# midi-switcher-dpdt.net
KiCad netlist of a schematic drawn in EAGLE
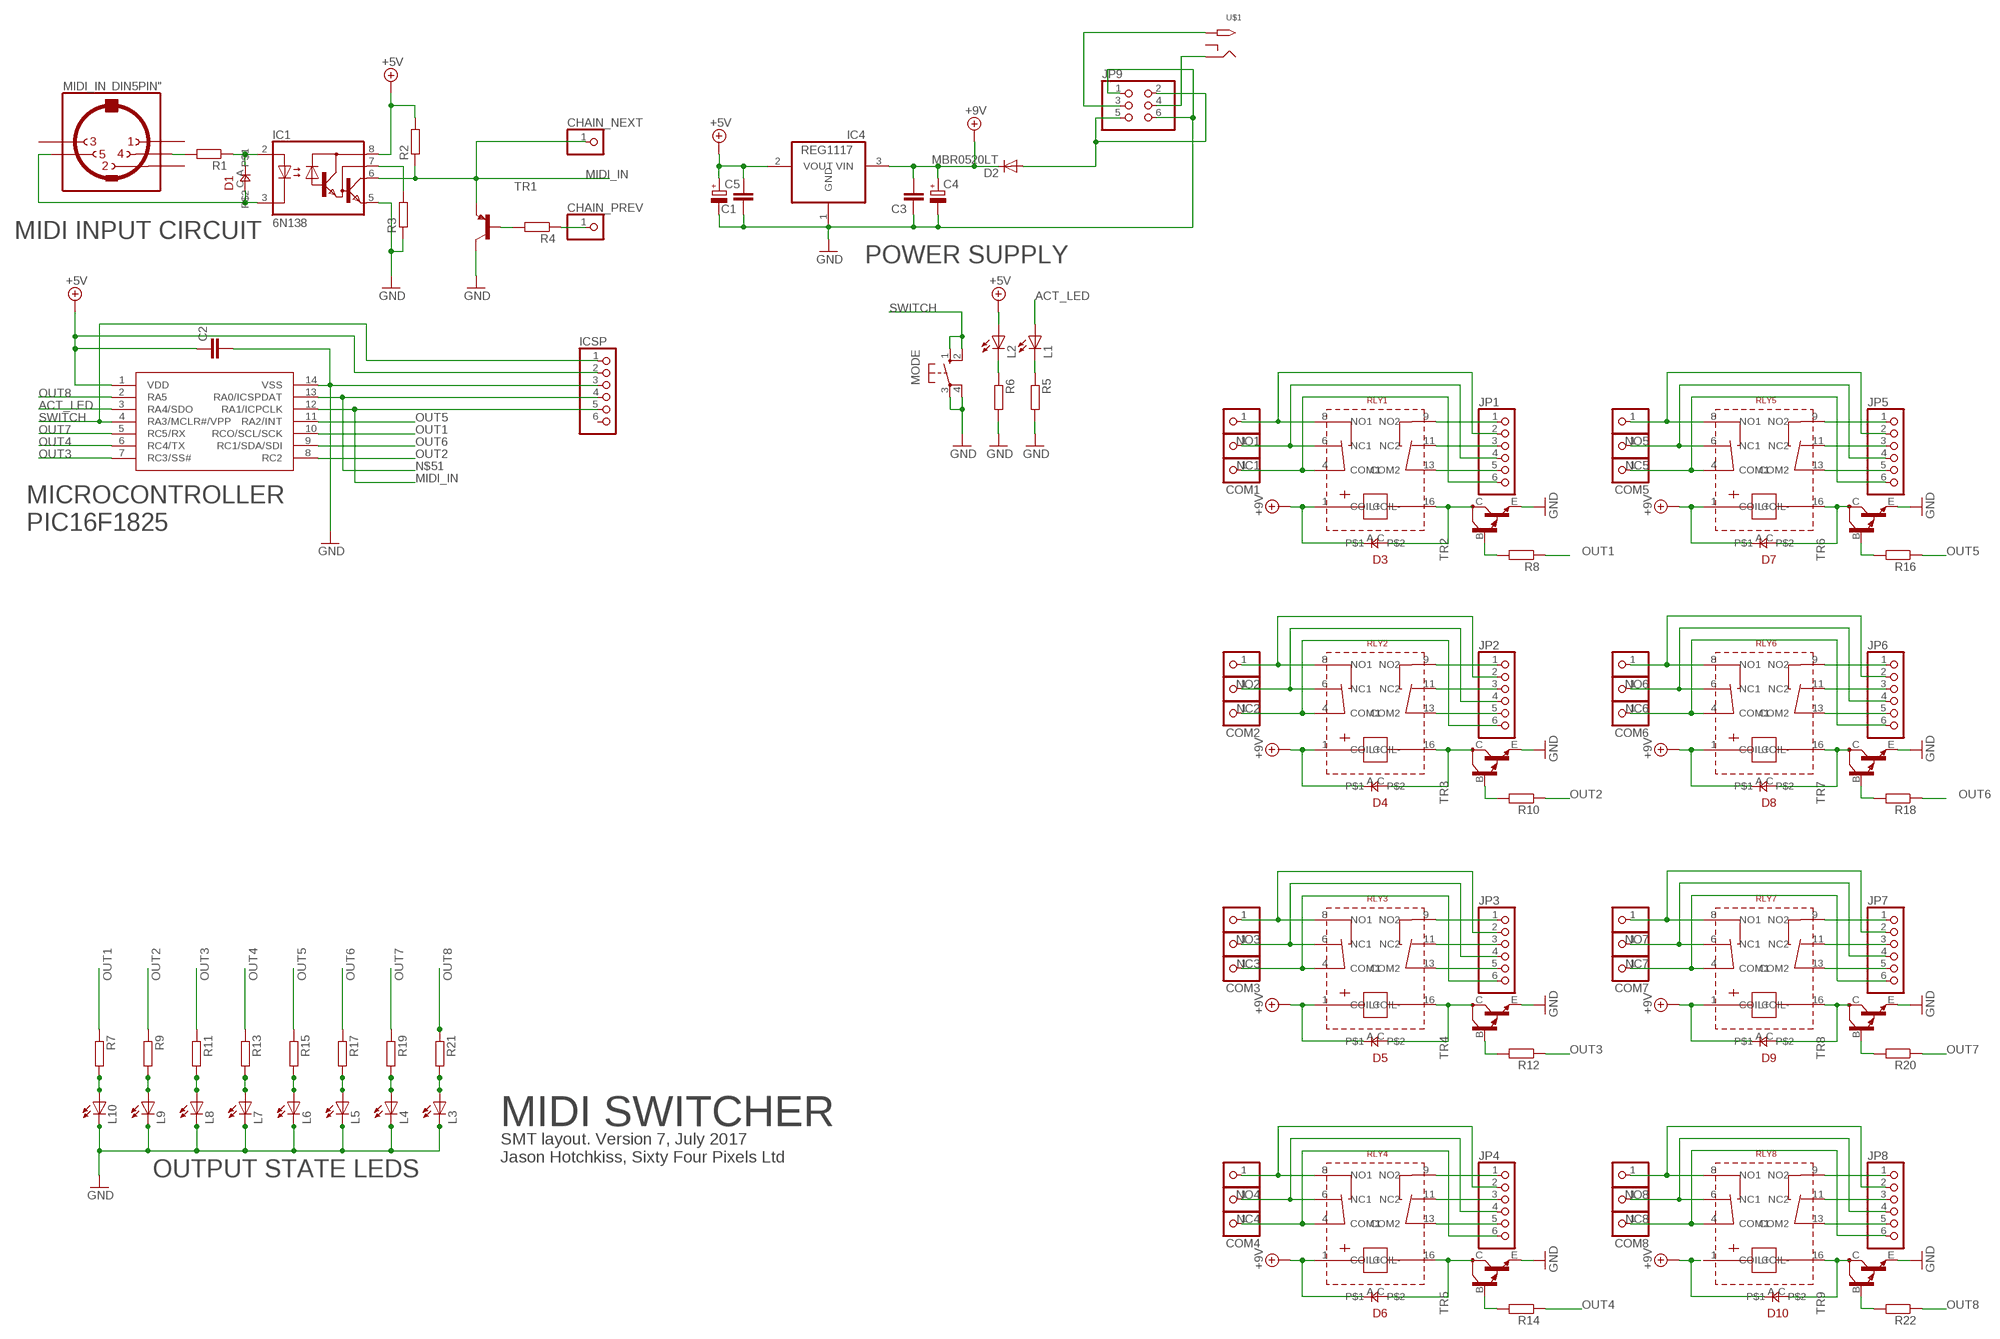
[diagram p0: schematic, sheet 1]

(export (version "E")
  (design (tool "Eeschema 10.0.6"))
  (components
    (comp (ref "C1")
      (value "C-EUC0805")
      (footprint "eagle-import:C0805")
      (libsource (lib "eagle-import") (part "C-EUC0805"))
    )
    (comp (ref "C2")
      (value "C-EUC0805")
      (footprint "eagle-import:C0805")
      (libsource (lib "eagle-import") (part "C-EUC0805"))
    )
    (comp (ref "C3")
      (value "C-EUC0805")
      (footprint "eagle-import:C0805")
      (libsource (lib "eagle-import") (part "C-EUC0805"))
    )
    (comp (ref "C4")
      (value "CPOL-EUE2,5-6E")
      (footprint "eagle-import:E2,5-6E")
      (libsource (lib "eagle-import") (part "CPOL-EUE2,5-6E"))
    )
    (comp (ref "C5")
      (value "CPOL-EUE2,5-6E")
      (footprint "eagle-import:E2,5-6E")
      (libsource (lib "eagle-import") (part "CPOL-EUE2,5-6E"))
    )
    (comp (ref "CHAIN_NEXT")
      (value "PINHD-1X1")
      (footprint "eagle-import:1X01")
      (libsource (lib "eagle-import") (part "PINHD-1X1"))
    )
    (comp (ref "CHAIN_PREV")
      (value "PINHD-1X1")
      (footprint "eagle-import:1X01")
      (libsource (lib "eagle-import") (part "PINHD-1X1"))
    )
    (comp (ref "COM1")
      (value "PINHD-1X1")
      (footprint "eagle-import:1X01")
      (libsource (lib "eagle-import") (part "PINHD-1X1"))
    )
    (comp (ref "COM2")
      (value "PINHD-1X1")
      (footprint "eagle-import:1X01")
      (libsource (lib "eagle-import") (part "PINHD-1X1"))
    )
    (comp (ref "COM3")
      (value "PINHD-1X1")
      (footprint "eagle-import:1X01")
      (libsource (lib "eagle-import") (part "PINHD-1X1"))
    )
    (comp (ref "COM4")
      (value "PINHD-1X1")
      (footprint "eagle-import:1X01")
      (libsource (lib "eagle-import") (part "PINHD-1X1"))
    )
    (comp (ref "COM5")
      (value "PINHD-1X1")
      (footprint "eagle-import:1X01")
      (libsource (lib "eagle-import") (part "PINHD-1X1"))
    )
    (comp (ref "COM6")
      (value "PINHD-1X1")
      (footprint "eagle-import:1X01")
      (libsource (lib "eagle-import") (part "PINHD-1X1"))
    )
    (comp (ref "COM7")
      (value "PINHD-1X1")
      (footprint "eagle-import:1X01")
      (libsource (lib "eagle-import") (part "PINHD-1X1"))
    )
    (comp (ref "COM8")
      (value "PINHD-1X1")
      (footprint "eagle-import:1X01")
      (libsource (lib "eagle-import") (part "PINHD-1X1"))
    )
    (comp (ref "D1")
      (value "0805DIODE")
      (footprint "eagle-import:0805DIODE")
      (libsource (lib "eagle-import") (part "0805DIODE"))
    )
    (comp (ref "D2")
      (value "MBR0520LT")
      (footprint "eagle-import:SOD123")
      (libsource (lib "eagle-import") (part "MBR0520LT"))
    )
    (comp (ref "D3")
      (value "0805DIODE")
      (footprint "eagle-import:0805DIODE")
      (libsource (lib "eagle-import") (part "0805DIODE"))
    )
    (comp (ref "D4")
      (value "0805DIODE")
      (footprint "eagle-import:0805DIODE")
      (libsource (lib "eagle-import") (part "0805DIODE"))
    )
    (comp (ref "D5")
      (value "0805DIODE")
      (footprint "eagle-import:0805DIODE")
      (libsource (lib "eagle-import") (part "0805DIODE"))
    )
    (comp (ref "D6")
      (value "0805DIODE")
      (footprint "eagle-import:0805DIODE")
      (libsource (lib "eagle-import") (part "0805DIODE"))
    )
    (comp (ref "D7")
      (value "0805DIODE")
      (footprint "eagle-import:0805DIODE")
      (libsource (lib "eagle-import") (part "0805DIODE"))
    )
    (comp (ref "D8")
      (value "0805DIODE")
      (footprint "eagle-import:0805DIODE")
      (libsource (lib "eagle-import") (part "0805DIODE"))
    )
    (comp (ref "D9")
      (value "0805DIODE")
      (footprint "eagle-import:0805DIODE")
      (libsource (lib "eagle-import") (part "0805DIODE"))
    )
    (comp (ref "D10")
      (value "0805DIODE")
      (footprint "eagle-import:0805DIODE")
      (libsource (lib "eagle-import") (part "0805DIODE"))
    )
    (comp (ref "IC1")
      (value "6N138")
      (footprint "eagle-import:DIL08")
      (libsource (lib "eagle-import") (part "6N138"))
    )
    (comp (ref "IC2")
      (value "PIC16F1825SO14")
      (footprint "eagle-import:SO14")
      (libsource (lib "eagle-import") (part "PIC16F1825SO14"))
    )
    (comp (ref "IC4")
      (value "REG1117")
      (footprint "eagle-import:SOT223")
      (libsource (lib "eagle-import") (part "REG1117"))
    )
    (comp (ref "ICSP")
      (value "HEADER-1X6")
      (footprint "eagle-import:1X06_OVAL")
      (libsource (lib "eagle-import") (part "HEADER-1X6"))
    )
    (comp (ref "JP1")
      (value "PINHD-1X6")
      (footprint "eagle-import:1X06")
      (libsource (lib "eagle-import") (part "PINHD-1X6"))
    )
    (comp (ref "JP2")
      (value "PINHD-1X6")
      (footprint "eagle-import:1X06")
      (libsource (lib "eagle-import") (part "PINHD-1X6"))
    )
    (comp (ref "JP3")
      (value "PINHD-1X6")
      (footprint "eagle-import:1X06")
      (libsource (lib "eagle-import") (part "PINHD-1X6"))
    )
    (comp (ref "JP4")
      (value "PINHD-1X6")
      (footprint "eagle-import:1X06")
      (libsource (lib "eagle-import") (part "PINHD-1X6"))
    )
    (comp (ref "JP5")
      (value "PINHD-1X6")
      (footprint "eagle-import:1X06")
      (libsource (lib "eagle-import") (part "PINHD-1X6"))
    )
    (comp (ref "JP6")
      (value "PINHD-1X6")
      (footprint "eagle-import:1X06")
      (libsource (lib "eagle-import") (part "PINHD-1X6"))
    )
    (comp (ref "JP7")
      (value "PINHD-1X6")
      (footprint "eagle-import:1X06")
      (libsource (lib "eagle-import") (part "PINHD-1X6"))
    )
    (comp (ref "JP8")
      (value "PINHD-1X6")
      (footprint "eagle-import:1X06")
      (libsource (lib "eagle-import") (part "PINHD-1X6"))
    )
    (comp (ref "JP9")
      (value "PINHD-2X3")
      (footprint "eagle-import:2X03")
      (libsource (lib "eagle-import") (part "PINHD-2X3"))
    )
    (comp (ref "L1")
      (value "LEDCHIP-LED0805")
      (footprint "eagle-import:CHIP-LED0805")
      (libsource (lib "eagle-import") (part "LEDCHIP-LED0805"))
    )
    (comp (ref "L2")
      (value "LEDCHIP-LED0805")
      (footprint "eagle-import:CHIP-LED0805")
      (libsource (lib "eagle-import") (part "LEDCHIP-LED0805"))
    )
    (comp (ref "L3")
      (value "LEDCHIP-LED0805")
      (footprint "eagle-import:CHIP-LED0805")
      (libsource (lib "eagle-import") (part "LEDCHIP-LED0805"))
    )
    (comp (ref "L4")
      (value "LEDCHIP-LED0805")
      (footprint "eagle-import:CHIP-LED0805")
      (libsource (lib "eagle-import") (part "LEDCHIP-LED0805"))
    )
    (comp (ref "L5")
      (value "LEDCHIP-LED0805")
      (footprint "eagle-import:CHIP-LED0805")
      (libsource (lib "eagle-import") (part "LEDCHIP-LED0805"))
    )
    (comp (ref "L6")
      (value "LEDCHIP-LED0805")
      (footprint "eagle-import:CHIP-LED0805")
      (libsource (lib "eagle-import") (part "LEDCHIP-LED0805"))
    )
    (comp (ref "L7")
      (value "LEDCHIP-LED0805")
      (footprint "eagle-import:CHIP-LED0805")
      (libsource (lib "eagle-import") (part "LEDCHIP-LED0805"))
    )
    (comp (ref "L8")
      (value "LEDCHIP-LED0805")
      (footprint "eagle-import:CHIP-LED0805")
      (libsource (lib "eagle-import") (part "LEDCHIP-LED0805"))
    )
    (comp (ref "L9")
      (value "LEDCHIP-LED0805")
      (footprint "eagle-import:CHIP-LED0805")
      (libsource (lib "eagle-import") (part "LEDCHIP-LED0805"))
    )
    (comp (ref "L10")
      (value "LEDCHIP-LED0805")
      (footprint "eagle-import:CHIP-LED0805")
      (libsource (lib "eagle-import") (part "LEDCHIP-LED0805"))
    )
    (comp (ref "MIDI_IN")
      (value "DIN5PIN\"")
      (footprint "eagle-import:TRUCONN90")
      (libsource (lib "eagle-import") (part "DIN5PIN{dblquote}"))
    )
    (comp (ref "MODE")
      (value "10-XX")
      (footprint "eagle-import:B3F-10XX")
      (libsource (lib "eagle-import") (part "10-XX"))
    )
    (comp (ref "NC1")
      (value "PINHD-1X1")
      (footprint "eagle-import:1X01")
      (libsource (lib "eagle-import") (part "PINHD-1X1"))
    )
    (comp (ref "NC2")
      (value "PINHD-1X1")
      (footprint "eagle-import:1X01")
      (libsource (lib "eagle-import") (part "PINHD-1X1"))
    )
    (comp (ref "NC3")
      (value "PINHD-1X1")
      (footprint "eagle-import:1X01")
      (libsource (lib "eagle-import") (part "PINHD-1X1"))
    )
    (comp (ref "NC4")
      (value "PINHD-1X1")
      (footprint "eagle-import:1X01")
      (libsource (lib "eagle-import") (part "PINHD-1X1"))
    )
    (comp (ref "NC5")
      (value "PINHD-1X1")
      (footprint "eagle-import:1X01")
      (libsource (lib "eagle-import") (part "PINHD-1X1"))
    )
    (comp (ref "NC6")
      (value "PINHD-1X1")
      (footprint "eagle-import:1X01")
      (libsource (lib "eagle-import") (part "PINHD-1X1"))
    )
    (comp (ref "NC7")
      (value "PINHD-1X1")
      (footprint "eagle-import:1X01")
      (libsource (lib "eagle-import") (part "PINHD-1X1"))
    )
    (comp (ref "NC8")
      (value "PINHD-1X1")
      (footprint "eagle-import:1X01")
      (libsource (lib "eagle-import") (part "PINHD-1X1"))
    )
    (comp (ref "NO1")
      (value "PINHD-1X1")
      (footprint "eagle-import:1X01")
      (libsource (lib "eagle-import") (part "PINHD-1X1"))
    )
    (comp (ref "NO2")
      (value "PINHD-1X1")
      (footprint "eagle-import:1X01")
      (libsource (lib "eagle-import") (part "PINHD-1X1"))
    )
    (comp (ref "NO3")
      (value "PINHD-1X1")
      (footprint "eagle-import:1X01")
      (libsource (lib "eagle-import") (part "PINHD-1X1"))
    )
    (comp (ref "NO4")
      (value "PINHD-1X1")
      (footprint "eagle-import:1X01")
      (libsource (lib "eagle-import") (part "PINHD-1X1"))
    )
    (comp (ref "NO5")
      (value "PINHD-1X1")
      (footprint "eagle-import:1X01")
      (libsource (lib "eagle-import") (part "PINHD-1X1"))
    )
    (comp (ref "NO6")
      (value "PINHD-1X1")
      (footprint "eagle-import:1X01")
      (libsource (lib "eagle-import") (part "PINHD-1X1"))
    )
    (comp (ref "NO7")
      (value "PINHD-1X1")
      (footprint "eagle-import:1X01")
      (libsource (lib "eagle-import") (part "PINHD-1X1"))
    )
    (comp (ref "NO8")
      (value "PINHD-1X1")
      (footprint "eagle-import:1X01")
      (libsource (lib "eagle-import") (part "PINHD-1X1"))
    )
    (comp (ref "R1")
      (value "R-EU_R0805")
      (footprint "eagle-import:R0805")
      (libsource (lib "eagle-import") (part "R-EU_R0805"))
    )
    (comp (ref "R2")
      (value "R-EU_R0805")
      (footprint "eagle-import:R0805")
      (libsource (lib "eagle-import") (part "R-EU_R0805"))
    )
    (comp (ref "R3")
      (value "R-EU_R0805")
      (footprint "eagle-import:R0805")
      (libsource (lib "eagle-import") (part "R-EU_R0805"))
    )
    (comp (ref "R4")
      (value "R-EU_R0805")
      (footprint "eagle-import:R0805")
      (libsource (lib "eagle-import") (part "R-EU_R0805"))
    )
    (comp (ref "R5")
      (value "R-EU_R0805")
      (footprint "eagle-import:R0805")
      (libsource (lib "eagle-import") (part "R-EU_R0805"))
    )
    (comp (ref "R6")
      (value "R-EU_R0805")
      (footprint "eagle-import:R0805")
      (libsource (lib "eagle-import") (part "R-EU_R0805"))
    )
    (comp (ref "R7")
      (value "R-EU_R0805")
      (footprint "eagle-import:R0805")
      (libsource (lib "eagle-import") (part "R-EU_R0805"))
    )
    (comp (ref "R8")
      (value "R-EU_R0805")
      (footprint "eagle-import:R0805")
      (libsource (lib "eagle-import") (part "R-EU_R0805"))
    )
    (comp (ref "R9")
      (value "R-EU_R0805")
      (footprint "eagle-import:R0805")
      (libsource (lib "eagle-import") (part "R-EU_R0805"))
    )
    (comp (ref "R10")
      (value "R-EU_R0805")
      (footprint "eagle-import:R0805")
      (libsource (lib "eagle-import") (part "R-EU_R0805"))
    )
    (comp (ref "R11")
      (value "R-EU_R0805")
      (footprint "eagle-import:R0805")
      (libsource (lib "eagle-import") (part "R-EU_R0805"))
    )
    (comp (ref "R12")
      (value "R-EU_R0805")
      (footprint "eagle-import:R0805")
      (libsource (lib "eagle-import") (part "R-EU_R0805"))
    )
    (comp (ref "R13")
      (value "R-EU_R0805")
      (footprint "eagle-import:R0805")
      (libsource (lib "eagle-import") (part "R-EU_R0805"))
    )
    (comp (ref "R14")
      (value "R-EU_R0805")
      (footprint "eagle-import:R0805")
      (libsource (lib "eagle-import") (part "R-EU_R0805"))
    )
    (comp (ref "R15")
      (value "R-EU_R0805")
      (footprint "eagle-import:R0805")
      (libsource (lib "eagle-import") (part "R-EU_R0805"))
    )
    (comp (ref "R16")
      (value "R-EU_R0805")
      (footprint "eagle-import:R0805")
      (libsource (lib "eagle-import") (part "R-EU_R0805"))
    )
    (comp (ref "R17")
      (value "R-EU_R0805")
      (footprint "eagle-import:R0805")
      (libsource (lib "eagle-import") (part "R-EU_R0805"))
    )
    (comp (ref "R18")
      (value "R-EU_R0805")
      (footprint "eagle-import:R0805")
      (libsource (lib "eagle-import") (part "R-EU_R0805"))
    )
    (comp (ref "R19")
      (value "R-EU_R0805")
      (footprint "eagle-import:R0805")
      (libsource (lib "eagle-import") (part "R-EU_R0805"))
    )
    (comp (ref "R20")
      (value "R-EU_R0805")
      (footprint "eagle-import:R0805")
      (libsource (lib "eagle-import") (part "R-EU_R0805"))
    )
    (comp (ref "R21")
      (value "R-EU_R0805")
      (footprint "eagle-import:R0805")
      (libsource (lib "eagle-import") (part "R-EU_R0805"))
    )
    (comp (ref "R22")
      (value "R-EU_R0805")
      (footprint "eagle-import:R0805")
      (libsource (lib "eagle-import") (part "R-EU_R0805"))
    )
    (comp (ref "RLY1")
      (value "HFD2RELAY")
      (footprint "eagle-import:HFD2RELAY")
      (libsource (lib "eagle-import") (part "HFD2RELAY"))
    )
    (comp (ref "RLY2")
      (value "HFD2RELAY")
      (footprint "eagle-import:HFD2RELAY")
      (libsource (lib "eagle-import") (part "HFD2RELAY"))
    )
    (comp (ref "RLY3")
      (value "HFD2RELAY")
      (footprint "eagle-import:HFD2RELAY")
      (libsource (lib "eagle-import") (part "HFD2RELAY"))
    )
    (comp (ref "RLY4")
      (value "HFD2RELAY")
      (footprint "eagle-import:HFD2RELAY")
      (libsource (lib "eagle-import") (part "HFD2RELAY"))
    )
    (comp (ref "RLY5")
      (value "HFD2RELAY")
      (footprint "eagle-import:HFD2RELAY")
      (libsource (lib "eagle-import") (part "HFD2RELAY"))
    )
    (comp (ref "RLY6")
      (value "HFD2RELAY")
      (footprint "eagle-import:HFD2RELAY")
      (libsource (lib "eagle-import") (part "HFD2RELAY"))
    )
    (comp (ref "RLY7")
      (value "HFD2RELAY")
      (footprint "eagle-import:HFD2RELAY")
      (libsource (lib "eagle-import") (part "HFD2RELAY"))
    )
    (comp (ref "RLY8")
      (value "HFD2RELAY")
      (footprint "eagle-import:HFD2RELAY")
      (libsource (lib "eagle-import") (part "HFD2RELAY"))
    )
    (comp (ref "TR1")
      (value "MMBT3906LT1-PNP-SOT23-BEC")
      (footprint "eagle-import:SOT23-BEC")
      (libsource (lib "eagle-import") (part "-PNP-SOT23-BECMMBT3906LT1"))
    )
    (comp (ref "TR2")
      (value "MMBTA13LT1-NPN_DARL-SOT23-BEC")
      (footprint "eagle-import:SOT23-BEC")
      (libsource (lib "eagle-import") (part "-NPN_DARL-SOT23-BECMMBTA13LT1"))
    )
    (comp (ref "TR3")
      (value "MMBTA13LT1-NPN_DARL-SOT23-BEC")
      (footprint "eagle-import:SOT23-BEC")
      (libsource (lib "eagle-import") (part "-NPN_DARL-SOT23-BECMMBTA13LT1"))
    )
    (comp (ref "TR4")
      (value "MMBTA13LT1-NPN_DARL-SOT23-BEC")
      (footprint "eagle-import:SOT23-BEC")
      (libsource (lib "eagle-import") (part "-NPN_DARL-SOT23-BECMMBTA13LT1"))
    )
    (comp (ref "TR5")
      (value "MMBTA13LT1-NPN_DARL-SOT23-BEC")
      (footprint "eagle-import:SOT23-BEC")
      (libsource (lib "eagle-import") (part "-NPN_DARL-SOT23-BECMMBTA13LT1"))
    )
    (comp (ref "TR6")
      (value "MMBTA13LT1-NPN_DARL-SOT23-BEC")
      (footprint "eagle-import:SOT23-BEC")
      (libsource (lib "eagle-import") (part "-NPN_DARL-SOT23-BECMMBTA13LT1"))
    )
    (comp (ref "TR7")
      (value "MMBTA13LT1-NPN_DARL-SOT23-BEC")
      (footprint "eagle-import:SOT23-BEC")
      (libsource (lib "eagle-import") (part "-NPN_DARL-SOT23-BECMMBTA13LT1"))
    )
    (comp (ref "TR8")
      (value "MMBTA13LT1-NPN_DARL-SOT23-BEC")
      (footprint "eagle-import:SOT23-BEC")
      (libsource (lib "eagle-import") (part "-NPN_DARL-SOT23-BECMMBTA13LT1"))
    )
    (comp (ref "TR9")
      (value "MMBTA13LT1-NPN_DARL-SOT23-BEC")
      (footprint "eagle-import:SOT23-BEC")
      (libsource (lib "eagle-import") (part "-NPN_DARL-SOT23-BECMMBTA13LT1"))
    )
    (comp (ref "U$1")
      (value "2.1MMJACKTHM")
      (footprint "eagle-import:PJ-102A")
      (libsource (lib "eagle-import") (part "2.1MMJACKTHM"))
    )
  )
  (nets
    (net (code "1") (name "+5V") (class "Default")
      (node (ref "C1") (pin "2") (pinfunction "2_2") (pintype "passive"))
      (node (ref "C2") (pin "1") (pinfunction "1_1") (pintype "passive"))
      (node (ref "C5") (pin "+") (pinfunction "+_+") (pintype "passive"))
      (node (ref "IC1") (pin "8") (pinfunction "VCC_8") (pintype "passive"))
      (node (ref "IC2") (pin "1") (pinfunction "VDD_1") (pintype "power_in"))
      (node (ref "IC4") (pin "2") (pinfunction "VOUT_2") (pintype "output"))
      (node (ref "ICSP") (pin "2") (pinfunction "2_2") (pintype "passive"))
      (node (ref "L2") (pin "A") (pinfunction "A_A") (pintype "passive"))
      (node (ref "R2") (pin "2") (pinfunction "2_2") (pintype "passive"))
    )
    (net (code "2") (name "+9V") (class "Default")
      (node (ref "C3") (pin "2") (pinfunction "2_2") (pintype "passive"))
      (node (ref "C4") (pin "+") (pinfunction "+_+") (pintype "passive"))
      (node (ref "D10") (pin "A") (pinfunction "P$2_A") (pintype "bidirectional"))
      (node (ref "D2") (pin "C") (pinfunction "C_C") (pintype "passive"))
      (node (ref "D3") (pin "A") (pinfunction "P$2_A") (pintype "bidirectional"))
      (node (ref "D4") (pin "A") (pinfunction "P$2_A") (pintype "bidirectional"))
      (node (ref "D5") (pin "A") (pinfunction "P$2_A") (pintype "bidirectional"))
      (node (ref "D6") (pin "A") (pinfunction "P$2_A") (pintype "bidirectional"))
      (node (ref "D7") (pin "A") (pinfunction "P$2_A") (pintype "bidirectional"))
      (node (ref "D8") (pin "A") (pinfunction "P$2_A") (pintype "bidirectional"))
      (node (ref "D9") (pin "A") (pinfunction "P$2_A") (pintype "bidirectional"))
      (node (ref "IC4") (pin "3") (pinfunction "VIN_3") (pintype "input"))
      (node (ref "RLY1") (pin "1") (pinfunction "COIL+_1") (pintype "bidirectional"))
      (node (ref "RLY2") (pin "1") (pinfunction "COIL+_1") (pintype "bidirectional"))
      (node (ref "RLY3") (pin "1") (pinfunction "COIL+_1") (pintype "bidirectional"))
      (node (ref "RLY4") (pin "1") (pinfunction "COIL+_1") (pintype "bidirectional"))
      (node (ref "RLY5") (pin "1") (pinfunction "COIL+_1") (pintype "bidirectional"))
      (node (ref "RLY6") (pin "1") (pinfunction "COIL+_1") (pintype "bidirectional"))
      (node (ref "RLY7") (pin "1") (pinfunction "COIL+_1") (pintype "bidirectional"))
      (node (ref "RLY8") (pin "1") (pinfunction "COIL+_1") (pintype "bidirectional"))
    )
    (net (code "3") (name "/ACT_LED") (class "Default")
      (node (ref "IC2") (pin "3") (pinfunction "RA4/SDO_3") (pintype "bidirectional"))
      (node (ref "L1") (pin "A") (pinfunction "A_A") (pintype "passive"))
    )
    (net (code "4") (name "/MIDI_IN") (class "Default")
      (node (ref "CHAIN_NEXT") (pin "1") (pinfunction "1_1") (pintype "passive"))
      (node (ref "IC1") (pin "6") (pinfunction "VO_6") (pintype "passive"))
      (node (ref "IC2") (pin "12") (pinfunction "RA1/ICPCLK_12") (pintype "bidirectional"))
      (node (ref "ICSP") (pin "5") (pinfunction "5_5") (pintype "passive"))
      (node (ref "R2") (pin "1") (pinfunction "1_1") (pintype "passive"))
      (node (ref "TR1") (pin "E") (pinfunction "E_E") (pintype "passive"))
    )
    (net (code "5") (name "/N$51") (class "Default")
      (node (ref "IC2") (pin "13") (pinfunction "RA0/ICSPDAT_13") (pintype "bidirectional"))
      (node (ref "ICSP") (pin "4") (pinfunction "4_4") (pintype "passive"))
    )
    (net (code "6") (name "/OUT1") (class "Default")
      (node (ref "IC2") (pin "10") (pinfunction "RCO/SCL/SCK_10") (pintype "bidirectional"))
      (node (ref "R7") (pin "1") (pinfunction "1_1") (pintype "passive"))
      (node (ref "R8") (pin "1") (pinfunction "1_1") (pintype "passive"))
    )
    (net (code "7") (name "/OUT2") (class "Default")
      (node (ref "IC2") (pin "8") (pinfunction "RC2_8") (pintype "bidirectional"))
      (node (ref "R10") (pin "1") (pinfunction "1_1") (pintype "passive"))
      (node (ref "R9") (pin "1") (pinfunction "1_1") (pintype "passive"))
    )
    (net (code "8") (name "/OUT3") (class "Default")
      (node (ref "IC2") (pin "7") (pinfunction "RC3/SS#_7") (pintype "bidirectional"))
      (node (ref "R11") (pin "1") (pinfunction "1_1") (pintype "passive"))
      (node (ref "R12") (pin "1") (pinfunction "1_1") (pintype "passive"))
    )
    (net (code "9") (name "/OUT4") (class "Default")
      (node (ref "IC2") (pin "6") (pinfunction "RC4/TX_6") (pintype "bidirectional"))
      (node (ref "R13") (pin "1") (pinfunction "1_1") (pintype "passive"))
      (node (ref "R14") (pin "1") (pinfunction "1_1") (pintype "passive"))
    )
    (net (code "10") (name "/OUT5") (class "Default")
      (node (ref "IC2") (pin "11") (pinfunction "RA2/INT_11") (pintype "bidirectional"))
      (node (ref "R15") (pin "1") (pinfunction "1_1") (pintype "passive"))
      (node (ref "R16") (pin "1") (pinfunction "1_1") (pintype "passive"))
    )
    (net (code "11") (name "/OUT6") (class "Default")
      (node (ref "IC2") (pin "9") (pinfunction "RC1/SDA/SDI_9") (pintype "bidirectional"))
      (node (ref "R17") (pin "1") (pinfunction "1_1") (pintype "passive"))
      (node (ref "R18") (pin "1") (pinfunction "1_1") (pintype "passive"))
    )
    (net (code "12") (name "/OUT7") (class "Default")
      (node (ref "IC2") (pin "5") (pinfunction "RC5/RX_5") (pintype "bidirectional"))
      (node (ref "R19") (pin "1") (pinfunction "1_1") (pintype "passive"))
      (node (ref "R20") (pin "1") (pinfunction "1_1") (pintype "passive"))
    )
    (net (code "13") (name "/OUT8") (class "Default")
      (node (ref "IC2") (pin "2") (pinfunction "RA5_2") (pintype "bidirectional"))
      (node (ref "R21") (pin "1") (pinfunction "1_1") (pintype "passive"))
      (node (ref "R22") (pin "1") (pinfunction "1_1") (pintype "passive"))
    )
    (net (code "14") (name "/SWITCH") (class "Default")
      (node (ref "IC2") (pin "4") (pinfunction "RA3/MCLR#/VPP_4") (pintype "input"))
      (node (ref "ICSP") (pin "1") (pinfunction "1_1") (pintype "passive"))
      (node (ref "MODE") (pin "1") (pinfunction "S_1") (pintype "passive"))
      (node (ref "MODE") (pin "2") (pinfunction "S1_2") (pintype "passive"))
    )
    (net (code "15") (name "GND") (class "Default")
      (node (ref "C1") (pin "1") (pinfunction "1_1") (pintype "passive"))
      (node (ref "C2") (pin "2") (pinfunction "2_2") (pintype "passive"))
      (node (ref "C3") (pin "1") (pinfunction "1_1") (pintype "passive"))
      (node (ref "C4") (pin "-") (pinfunction "-_-") (pintype "passive"))
      (node (ref "C5") (pin "-") (pinfunction "-_-") (pintype "passive"))
      (node (ref "IC1") (pin "5") (pinfunction "GND_5") (pintype "passive"))
      (node (ref "IC2") (pin "14") (pinfunction "VSS_14") (pintype "power_in"))
      (node (ref "IC4") (pin "1") (pinfunction "GND_1") (pintype "power_in"))
      (node (ref "ICSP") (pin "3") (pinfunction "3_3") (pintype "passive"))
      (node (ref "JP9") (pin "1") (pinfunction "1_1") (pintype "passive"))
      (node (ref "JP9") (pin "6") (pinfunction "6_6") (pintype "passive"))
      (node (ref "L10") (pin "C") (pinfunction "C_C") (pintype "passive"))
      (node (ref "L3") (pin "C") (pinfunction "C_C") (pintype "passive"))
      (node (ref "L4") (pin "C") (pinfunction "C_C") (pintype "passive"))
      (node (ref "L5") (pin "C") (pinfunction "C_C") (pintype "passive"))
      (node (ref "L6") (pin "C") (pinfunction "C_C") (pintype "passive"))
      (node (ref "L7") (pin "C") (pinfunction "C_C") (pintype "passive"))
      (node (ref "L8") (pin "C") (pinfunction "C_C") (pintype "passive"))
      (node (ref "L9") (pin "C") (pinfunction "C_C") (pintype "passive"))
      (node (ref "MODE") (pin "3") (pinfunction "P_3") (pintype "passive"))
      (node (ref "MODE") (pin "4") (pinfunction "P1_4") (pintype "passive"))
      (node (ref "R3") (pin "1") (pinfunction "1_1") (pintype "passive"))
      (node (ref "R5") (pin "2") (pinfunction "2_2") (pintype "passive"))
      (node (ref "R6") (pin "2") (pinfunction "2_2") (pintype "passive"))
      (node (ref "TR1") (pin "C") (pinfunction "C_C") (pintype "passive"))
      (node (ref "TR2") (pin "E") (pinfunction "E_E") (pintype "passive"))
      (node (ref "TR3") (pin "E") (pinfunction "E_E") (pintype "passive"))
      (node (ref "TR4") (pin "E") (pinfunction "E_E") (pintype "passive"))
      (node (ref "TR5") (pin "E") (pinfunction "E_E") (pintype "passive"))
      (node (ref "TR6") (pin "E") (pinfunction "E_E") (pintype "passive"))
      (node (ref "TR7") (pin "E") (pinfunction "E_E") (pintype "passive"))
      (node (ref "TR8") (pin "E") (pinfunction "E_E") (pintype "passive"))
      (node (ref "TR9") (pin "E") (pinfunction "E_E") (pintype "passive"))
    )
    (net (code "16") (name "Net-(CHAIN_PREV-Pad1)") (class "Default")
      (node (ref "CHAIN_PREV") (pin "1") (pinfunction "1_1") (pintype "passive"))
      (node (ref "R4") (pin "1") (pinfunction "1_1") (pintype "passive"))
    )
    (net (code "17") (name "Net-(D1-P$1)") (class "Default")
      (node (ref "D1") (pin "C") (pinfunction "P$1_C") (pintype "bidirectional"))
      (node (ref "IC1") (pin "3") (pinfunction "C_3") (pintype "passive"))
      (node (ref "MIDI_IN") (pin "5") (pinfunction "5_5") (pintype "passive"))
    )
    (net (code "18") (name "Net-(D1-P$2)") (class "Default")
      (node (ref "D1") (pin "A") (pinfunction "P$2_A") (pintype "bidirectional"))
      (node (ref "IC1") (pin "2") (pinfunction "A_2") (pintype "passive"))
      (node (ref "R1") (pin "1") (pinfunction "1_1") (pintype "passive"))
    )
    (net (code "19") (name "Net-(D2-PadA)") (class "Default")
      (node (ref "D2") (pin "A") (pinfunction "A_A") (pintype "passive"))
      (node (ref "JP9") (pin "2") (pinfunction "2_2") (pintype "passive"))
      (node (ref "JP9") (pin "5") (pinfunction "5_5") (pintype "passive"))
    )
    (net (code "20") (name "Net-(D3-P$1)") (class "Default")
      (node (ref "D3") (pin "C") (pinfunction "P$1_C") (pintype "bidirectional"))
      (node (ref "RLY1") (pin "16") (pinfunction "COIL-_16") (pintype "bidirectional"))
      (node (ref "TR2") (pin "C") (pinfunction "C_C") (pintype "passive"))
    )
    (net (code "21") (name "Net-(D4-P$1)") (class "Default")
      (node (ref "D4") (pin "C") (pinfunction "P$1_C") (pintype "bidirectional"))
      (node (ref "RLY2") (pin "16") (pinfunction "COIL-_16") (pintype "bidirectional"))
      (node (ref "TR3") (pin "C") (pinfunction "C_C") (pintype "passive"))
    )
    (net (code "22") (name "Net-(D5-P$1)") (class "Default")
      (node (ref "D5") (pin "C") (pinfunction "P$1_C") (pintype "bidirectional"))
      (node (ref "RLY3") (pin "16") (pinfunction "COIL-_16") (pintype "bidirectional"))
      (node (ref "TR4") (pin "C") (pinfunction "C_C") (pintype "passive"))
    )
    (net (code "23") (name "Net-(D6-P$1)") (class "Default")
      (node (ref "D6") (pin "C") (pinfunction "P$1_C") (pintype "bidirectional"))
      (node (ref "RLY4") (pin "16") (pinfunction "COIL-_16") (pintype "bidirectional"))
      (node (ref "TR5") (pin "C") (pinfunction "C_C") (pintype "passive"))
    )
    (net (code "24") (name "Net-(D7-P$1)") (class "Default")
      (node (ref "D7") (pin "C") (pinfunction "P$1_C") (pintype "bidirectional"))
      (node (ref "RLY5") (pin "16") (pinfunction "COIL-_16") (pintype "bidirectional"))
      (node (ref "TR6") (pin "C") (pinfunction "C_C") (pintype "passive"))
    )
    (net (code "25") (name "Net-(D8-P$1)") (class "Default")
      (node (ref "D8") (pin "C") (pinfunction "P$1_C") (pintype "bidirectional"))
      (node (ref "RLY6") (pin "16") (pinfunction "COIL-_16") (pintype "bidirectional"))
      (node (ref "TR7") (pin "C") (pinfunction "C_C") (pintype "passive"))
    )
    (net (code "26") (name "Net-(D9-P$1)") (class "Default")
      (node (ref "D9") (pin "C") (pinfunction "P$1_C") (pintype "bidirectional"))
      (node (ref "RLY7") (pin "16") (pinfunction "COIL-_16") (pintype "bidirectional"))
      (node (ref "TR8") (pin "C") (pinfunction "C_C") (pintype "passive"))
    )
    (net (code "27") (name "Net-(D10-P$1)") (class "Default")
      (node (ref "D10") (pin "C") (pinfunction "P$1_C") (pintype "bidirectional"))
      (node (ref "RLY8") (pin "16") (pinfunction "COIL-_16") (pintype "bidirectional"))
      (node (ref "TR9") (pin "C") (pinfunction "C_C") (pintype "passive"))
    )
    (net (code "28") (name "Net-(IC1-VB)") (class "Default")
      (node (ref "IC1") (pin "7") (pinfunction "VB_7") (pintype "passive"))
      (node (ref "R3") (pin "2") (pinfunction "2_2") (pintype "passive"))
    )
    (net (code "29") (name "Net-(JP9-Pad3)") (class "Default")
      (node (ref "JP9") (pin "3") (pinfunction "3_3") (pintype "passive"))
      (node (ref "U$1") (pin "TIP") (pinfunction "TIP_TIP") (pintype "bidirectional"))
    )
    (net (code "30") (name "Net-(JP9-Pad4)") (class "Default")
      (node (ref "JP9") (pin "4") (pinfunction "4_4") (pintype "passive"))
      (node (ref "U$1") (pin "RING") (pinfunction "RING_RING") (pintype "bidirectional"))
    )
    (net (code "31") (name "Net-(L1-PadC)") (class "Default")
      (node (ref "L1") (pin "C") (pinfunction "C_C") (pintype "passive"))
      (node (ref "R5") (pin "1") (pinfunction "1_1") (pintype "passive"))
    )
    (net (code "32") (name "Net-(L2-PadC)") (class "Default")
      (node (ref "L2") (pin "C") (pinfunction "C_C") (pintype "passive"))
      (node (ref "R6") (pin "1") (pinfunction "1_1") (pintype "passive"))
    )
    (net (code "33") (name "Net-(L3-PadA)") (class "Default")
      (node (ref "L3") (pin "A") (pinfunction "A_A") (pintype "passive"))
      (node (ref "R21") (pin "2") (pinfunction "2_2") (pintype "passive"))
    )
    (net (code "34") (name "Net-(L4-PadA)") (class "Default")
      (node (ref "L4") (pin "A") (pinfunction "A_A") (pintype "passive"))
      (node (ref "R19") (pin "2") (pinfunction "2_2") (pintype "passive"))
    )
    (net (code "35") (name "Net-(L5-PadA)") (class "Default")
      (node (ref "L5") (pin "A") (pinfunction "A_A") (pintype "passive"))
      (node (ref "R17") (pin "2") (pinfunction "2_2") (pintype "passive"))
    )
    (net (code "36") (name "Net-(L6-PadA)") (class "Default")
      (node (ref "L6") (pin "A") (pinfunction "A_A") (pintype "passive"))
      (node (ref "R15") (pin "2") (pinfunction "2_2") (pintype "passive"))
    )
    (net (code "37") (name "Net-(L7-PadA)") (class "Default")
      (node (ref "L7") (pin "A") (pinfunction "A_A") (pintype "passive"))
      (node (ref "R13") (pin "2") (pinfunction "2_2") (pintype "passive"))
    )
    (net (code "38") (name "Net-(L8-PadA)") (class "Default")
      (node (ref "L8") (pin "A") (pinfunction "A_A") (pintype "passive"))
      (node (ref "R11") (pin "2") (pinfunction "2_2") (pintype "passive"))
    )
    (net (code "39") (name "Net-(L9-PadA)") (class "Default")
      (node (ref "L9") (pin "A") (pinfunction "A_A") (pintype "passive"))
      (node (ref "R9") (pin "2") (pinfunction "2_2") (pintype "passive"))
    )
    (net (code "40") (name "Net-(L10-PadA)") (class "Default")
      (node (ref "L10") (pin "A") (pinfunction "A_A") (pintype "passive"))
      (node (ref "R7") (pin "2") (pinfunction "2_2") (pintype "passive"))
    )
    (net (code "41") (name "Net-(MIDI_IN-Pad4)") (class "Default")
      (node (ref "MIDI_IN") (pin "4") (pinfunction "4_4") (pintype "passive"))
      (node (ref "R1") (pin "2") (pinfunction "2_2") (pintype "passive"))
    )
    (net (code "42") (name "Net-(R4-Pad2)") (class "Default")
      (node (ref "R4") (pin "2") (pinfunction "2_2") (pintype "passive"))
      (node (ref "TR1") (pin "B") (pinfunction "B_B") (pintype "passive"))
    )
    (net (code "43") (name "Net-(R8-Pad2)") (class "Default")
      (node (ref "R8") (pin "2") (pinfunction "2_2") (pintype "passive"))
      (node (ref "TR2") (pin "B") (pinfunction "B_B") (pintype "passive"))
    )
    (net (code "44") (name "Net-(R10-Pad2)") (class "Default")
      (node (ref "R10") (pin "2") (pinfunction "2_2") (pintype "passive"))
      (node (ref "TR3") (pin "B") (pinfunction "B_B") (pintype "passive"))
    )
    (net (code "45") (name "Net-(R12-Pad2)") (class "Default")
      (node (ref "R12") (pin "2") (pinfunction "2_2") (pintype "passive"))
      (node (ref "TR4") (pin "B") (pinfunction "B_B") (pintype "passive"))
    )
    (net (code "46") (name "Net-(R14-Pad2)") (class "Default")
      (node (ref "R14") (pin "2") (pinfunction "2_2") (pintype "passive"))
      (node (ref "TR5") (pin "B") (pinfunction "B_B") (pintype "passive"))
    )
    (net (code "47") (name "Net-(R16-Pad2)") (class "Default")
      (node (ref "R16") (pin "2") (pinfunction "2_2") (pintype "passive"))
      (node (ref "TR6") (pin "B") (pinfunction "B_B") (pintype "passive"))
    )
    (net (code "48") (name "Net-(R18-Pad2)") (class "Default")
      (node (ref "R18") (pin "2") (pinfunction "2_2") (pintype "passive"))
      (node (ref "TR7") (pin "B") (pinfunction "B_B") (pintype "passive"))
    )
    (net (code "49") (name "Net-(R20-Pad2)") (class "Default")
      (node (ref "R20") (pin "2") (pinfunction "2_2") (pintype "passive"))
      (node (ref "TR8") (pin "B") (pinfunction "B_B") (pintype "passive"))
    )
    (net (code "50") (name "Net-(R22-Pad2)") (class "Default")
      (node (ref "R22") (pin "2") (pinfunction "2_2") (pintype "passive"))
      (node (ref "TR9") (pin "B") (pinfunction "B_B") (pintype "passive"))
    )
    (net (code "51") (name "Net-(RLY1-COM1)") (class "Default")
      (node (ref "COM1") (pin "1") (pinfunction "1_1") (pintype "passive"))
      (node (ref "JP1") (pin "6") (pinfunction "6_6") (pintype "passive"))
      (node (ref "RLY1") (pin "4") (pinfunction "COM1_4") (pintype "bidirectional"))
    )
    (net (code "52") (name "Net-(RLY1-COM2)") (class "Default")
      (node (ref "JP1") (pin "5") (pinfunction "5_5") (pintype "passive"))
      (node (ref "RLY1") (pin "13") (pinfunction "COM2_13") (pintype "bidirectional"))
    )
    (net (code "53") (name "Net-(RLY1-NC1)") (class "Default")
      (node (ref "JP1") (pin "4") (pinfunction "4_4") (pintype "passive"))
      (node (ref "NC1") (pin "1") (pinfunction "1_1") (pintype "passive"))
      (node (ref "RLY1") (pin "6") (pinfunction "NC1_6") (pintype "bidirectional"))
    )
    (net (code "54") (name "Net-(RLY1-NC2)") (class "Default")
      (node (ref "JP1") (pin "3") (pinfunction "3_3") (pintype "passive"))
      (node (ref "RLY1") (pin "11") (pinfunction "NC2_11") (pintype "bidirectional"))
    )
    (net (code "55") (name "Net-(RLY1-NO1)") (class "Default")
      (node (ref "JP1") (pin "2") (pinfunction "2_2") (pintype "passive"))
      (node (ref "NO1") (pin "1") (pinfunction "1_1") (pintype "passive"))
      (node (ref "RLY1") (pin "8") (pinfunction "NO1_8") (pintype "bidirectional"))
    )
    (net (code "56") (name "Net-(RLY1-NO2)") (class "Default")
      (node (ref "JP1") (pin "1") (pinfunction "1_1") (pintype "passive"))
      (node (ref "RLY1") (pin "9") (pinfunction "NO2_9") (pintype "bidirectional"))
    )
    (net (code "57") (name "Net-(RLY2-COM1)") (class "Default")
      (node (ref "COM2") (pin "1") (pinfunction "1_1") (pintype "passive"))
      (node (ref "JP2") (pin "6") (pinfunction "6_6") (pintype "passive"))
      (node (ref "RLY2") (pin "4") (pinfunction "COM1_4") (pintype "bidirectional"))
    )
    (net (code "58") (name "Net-(RLY2-COM2)") (class "Default")
      (node (ref "JP2") (pin "5") (pinfunction "5_5") (pintype "passive"))
      (node (ref "RLY2") (pin "13") (pinfunction "COM2_13") (pintype "bidirectional"))
    )
    (net (code "59") (name "Net-(RLY2-NC1)") (class "Default")
      (node (ref "JP2") (pin "4") (pinfunction "4_4") (pintype "passive"))
      (node (ref "NC2") (pin "1") (pinfunction "1_1") (pintype "passive"))
      (node (ref "RLY2") (pin "6") (pinfunction "NC1_6") (pintype "bidirectional"))
    )
    (net (code "60") (name "Net-(RLY2-NC2)") (class "Default")
      (node (ref "JP2") (pin "3") (pinfunction "3_3") (pintype "passive"))
      (node (ref "RLY2") (pin "11") (pinfunction "NC2_11") (pintype "bidirectional"))
    )
    (net (code "61") (name "Net-(RLY2-NO1)") (class "Default")
      (node (ref "JP2") (pin "2") (pinfunction "2_2") (pintype "passive"))
      (node (ref "NO2") (pin "1") (pinfunction "1_1") (pintype "passive"))
      (node (ref "RLY2") (pin "8") (pinfunction "NO1_8") (pintype "bidirectional"))
    )
    (net (code "62") (name "Net-(RLY2-NO2)") (class "Default")
      (node (ref "JP2") (pin "1") (pinfunction "1_1") (pintype "passive"))
      (node (ref "RLY2") (pin "9") (pinfunction "NO2_9") (pintype "bidirectional"))
    )
    (net (code "63") (name "Net-(RLY3-COM1)") (class "Default")
      (node (ref "COM3") (pin "1") (pinfunction "1_1") (pintype "passive"))
      (node (ref "JP3") (pin "6") (pinfunction "6_6") (pintype "passive"))
      (node (ref "RLY3") (pin "4") (pinfunction "COM1_4") (pintype "bidirectional"))
    )
    (net (code "64") (name "Net-(RLY3-COM2)") (class "Default")
      (node (ref "JP3") (pin "5") (pinfunction "5_5") (pintype "passive"))
      (node (ref "RLY3") (pin "13") (pinfunction "COM2_13") (pintype "bidirectional"))
    )
    (net (code "65") (name "Net-(RLY3-NC1)") (class "Default")
      (node (ref "JP3") (pin "4") (pinfunction "4_4") (pintype "passive"))
      (node (ref "NC3") (pin "1") (pinfunction "1_1") (pintype "passive"))
      (node (ref "RLY3") (pin "6") (pinfunction "NC1_6") (pintype "bidirectional"))
    )
    (net (code "66") (name "Net-(RLY3-NC2)") (class "Default")
      (node (ref "JP3") (pin "3") (pinfunction "3_3") (pintype "passive"))
      (node (ref "RLY3") (pin "11") (pinfunction "NC2_11") (pintype "bidirectional"))
    )
    (net (code "67") (name "Net-(RLY3-NO1)") (class "Default")
      (node (ref "JP3") (pin "2") (pinfunction "2_2") (pintype "passive"))
      (node (ref "NO3") (pin "1") (pinfunction "1_1") (pintype "passive"))
      (node (ref "RLY3") (pin "8") (pinfunction "NO1_8") (pintype "bidirectional"))
    )
    (net (code "68") (name "Net-(RLY3-NO2)") (class "Default")
      (node (ref "JP3") (pin "1") (pinfunction "1_1") (pintype "passive"))
      (node (ref "RLY3") (pin "9") (pinfunction "NO2_9") (pintype "bidirectional"))
    )
    (net (code "69") (name "Net-(RLY4-COM1)") (class "Default")
      (node (ref "COM4") (pin "1") (pinfunction "1_1") (pintype "passive"))
      (node (ref "JP4") (pin "6") (pinfunction "6_6") (pintype "passive"))
      (node (ref "RLY4") (pin "4") (pinfunction "COM1_4") (pintype "bidirectional"))
    )
    (net (code "70") (name "Net-(RLY4-COM2)") (class "Default")
      (node (ref "JP4") (pin "5") (pinfunction "5_5") (pintype "passive"))
      (node (ref "RLY4") (pin "13") (pinfunction "COM2_13") (pintype "bidirectional"))
    )
    (net (code "71") (name "Net-(RLY4-NC1)") (class "Default")
      (node (ref "JP4") (pin "4") (pinfunction "4_4") (pintype "passive"))
      (node (ref "NC4") (pin "1") (pinfunction "1_1") (pintype "passive"))
      (node (ref "RLY4") (pin "6") (pinfunction "NC1_6") (pintype "bidirectional"))
    )
    (net (code "72") (name "Net-(RLY4-NC2)") (class "Default")
      (node (ref "JP4") (pin "3") (pinfunction "3_3") (pintype "passive"))
      (node (ref "RLY4") (pin "11") (pinfunction "NC2_11") (pintype "bidirectional"))
    )
    (net (code "73") (name "Net-(RLY4-NO1)") (class "Default")
      (node (ref "JP4") (pin "2") (pinfunction "2_2") (pintype "passive"))
      (node (ref "NO4") (pin "1") (pinfunction "1_1") (pintype "passive"))
      (node (ref "RLY4") (pin "8") (pinfunction "NO1_8") (pintype "bidirectional"))
    )
    (net (code "74") (name "Net-(RLY4-NO2)") (class "Default")
      (node (ref "JP4") (pin "1") (pinfunction "1_1") (pintype "passive"))
      (node (ref "RLY4") (pin "9") (pinfunction "NO2_9") (pintype "bidirectional"))
    )
    (net (code "75") (name "Net-(RLY5-COM1)") (class "Default")
      (node (ref "COM5") (pin "1") (pinfunction "1_1") (pintype "passive"))
      (node (ref "JP5") (pin "6") (pinfunction "6_6") (pintype "passive"))
      (node (ref "RLY5") (pin "4") (pinfunction "COM1_4") (pintype "bidirectional"))
    )
    (net (code "76") (name "Net-(RLY5-COM2)") (class "Default")
      (node (ref "JP5") (pin "5") (pinfunction "5_5") (pintype "passive"))
      (node (ref "RLY5") (pin "13") (pinfunction "COM2_13") (pintype "bidirectional"))
    )
    (net (code "77") (name "Net-(RLY5-NC1)") (class "Default")
      (node (ref "JP5") (pin "4") (pinfunction "4_4") (pintype "passive"))
      (node (ref "NC5") (pin "1") (pinfunction "1_1") (pintype "passive"))
      (node (ref "RLY5") (pin "6") (pinfunction "NC1_6") (pintype "bidirectional"))
    )
    (net (code "78") (name "Net-(RLY5-NC2)") (class "Default")
      (node (ref "JP5") (pin "3") (pinfunction "3_3") (pintype "passive"))
      (node (ref "RLY5") (pin "11") (pinfunction "NC2_11") (pintype "bidirectional"))
    )
    (net (code "79") (name "Net-(RLY5-NO1)") (class "Default")
      (node (ref "JP5") (pin "2") (pinfunction "2_2") (pintype "passive"))
      (node (ref "NO5") (pin "1") (pinfunction "1_1") (pintype "passive"))
      (node (ref "RLY5") (pin "8") (pinfunction "NO1_8") (pintype "bidirectional"))
    )
    (net (code "80") (name "Net-(RLY5-NO2)") (class "Default")
      (node (ref "JP5") (pin "1") (pinfunction "1_1") (pintype "passive"))
      (node (ref "RLY5") (pin "9") (pinfunction "NO2_9") (pintype "bidirectional"))
    )
    (net (code "81") (name "Net-(RLY6-COM1)") (class "Default")
      (node (ref "COM6") (pin "1") (pinfunction "1_1") (pintype "passive"))
      (node (ref "JP6") (pin "6") (pinfunction "6_6") (pintype "passive"))
      (node (ref "RLY6") (pin "4") (pinfunction "COM1_4") (pintype "bidirectional"))
    )
    (net (code "82") (name "Net-(RLY6-COM2)") (class "Default")
      (node (ref "JP6") (pin "5") (pinfunction "5_5") (pintype "passive"))
      (node (ref "RLY6") (pin "13") (pinfunction "COM2_13") (pintype "bidirectional"))
    )
    (net (code "83") (name "Net-(RLY6-NC1)") (class "Default")
      (node (ref "JP6") (pin "4") (pinfunction "4_4") (pintype "passive"))
      (node (ref "NC6") (pin "1") (pinfunction "1_1") (pintype "passive"))
      (node (ref "RLY6") (pin "6") (pinfunction "NC1_6") (pintype "bidirectional"))
    )
    (net (code "84") (name "Net-(RLY6-NC2)") (class "Default")
      (node (ref "JP6") (pin "3") (pinfunction "3_3") (pintype "passive"))
      (node (ref "RLY6") (pin "11") (pinfunction "NC2_11") (pintype "bidirectional"))
    )
    (net (code "85") (name "Net-(RLY6-NO1)") (class "Default")
      (node (ref "JP6") (pin "2") (pinfunction "2_2") (pintype "passive"))
      (node (ref "NO6") (pin "1") (pinfunction "1_1") (pintype "passive"))
      (node (ref "RLY6") (pin "8") (pinfunction "NO1_8") (pintype "bidirectional"))
    )
    (net (code "86") (name "Net-(RLY6-NO2)") (class "Default")
      (node (ref "JP6") (pin "1") (pinfunction "1_1") (pintype "passive"))
      (node (ref "RLY6") (pin "9") (pinfunction "NO2_9") (pintype "bidirectional"))
    )
    (net (code "87") (name "Net-(RLY7-COM1)") (class "Default")
      (node (ref "COM7") (pin "1") (pinfunction "1_1") (pintype "passive"))
      (node (ref "JP7") (pin "6") (pinfunction "6_6") (pintype "passive"))
      (node (ref "RLY7") (pin "4") (pinfunction "COM1_4") (pintype "bidirectional"))
    )
    (net (code "88") (name "Net-(RLY7-COM2)") (class "Default")
      (node (ref "JP7") (pin "5") (pinfunction "5_5") (pintype "passive"))
      (node (ref "RLY7") (pin "13") (pinfunction "COM2_13") (pintype "bidirectional"))
    )
    (net (code "89") (name "Net-(RLY7-NC1)") (class "Default")
      (node (ref "JP7") (pin "4") (pinfunction "4_4") (pintype "passive"))
      (node (ref "NC7") (pin "1") (pinfunction "1_1") (pintype "passive"))
      (node (ref "RLY7") (pin "6") (pinfunction "NC1_6") (pintype "bidirectional"))
    )
    (net (code "90") (name "Net-(RLY7-NC2)") (class "Default")
      (node (ref "JP7") (pin "3") (pinfunction "3_3") (pintype "passive"))
      (node (ref "RLY7") (pin "11") (pinfunction "NC2_11") (pintype "bidirectional"))
    )
    (net (code "91") (name "Net-(RLY7-NO1)") (class "Default")
      (node (ref "JP7") (pin "2") (pinfunction "2_2") (pintype "passive"))
      (node (ref "NO7") (pin "1") (pinfunction "1_1") (pintype "passive"))
      (node (ref "RLY7") (pin "8") (pinfunction "NO1_8") (pintype "bidirectional"))
    )
    (net (code "92") (name "Net-(RLY7-NO2)") (class "Default")
      (node (ref "JP7") (pin "1") (pinfunction "1_1") (pintype "passive"))
      (node (ref "RLY7") (pin "9") (pinfunction "NO2_9") (pintype "bidirectional"))
    )
    (net (code "93") (name "Net-(RLY8-COM1)") (class "Default")
      (node (ref "COM8") (pin "1") (pinfunction "1_1") (pintype "passive"))
      (node (ref "JP8") (pin "6") (pinfunction "6_6") (pintype "passive"))
      (node (ref "RLY8") (pin "4") (pinfunction "COM1_4") (pintype "bidirectional"))
    )
    (net (code "94") (name "Net-(RLY8-COM2)") (class "Default")
      (node (ref "JP8") (pin "5") (pinfunction "5_5") (pintype "passive"))
      (node (ref "RLY8") (pin "13") (pinfunction "COM2_13") (pintype "bidirectional"))
    )
    (net (code "95") (name "Net-(RLY8-NC1)") (class "Default")
      (node (ref "JP8") (pin "4") (pinfunction "4_4") (pintype "passive"))
      (node (ref "NC8") (pin "1") (pinfunction "1_1") (pintype "passive"))
      (node (ref "RLY8") (pin "6") (pinfunction "NC1_6") (pintype "bidirectional"))
    )
    (net (code "96") (name "Net-(RLY8-NC2)") (class "Default")
      (node (ref "JP8") (pin "3") (pinfunction "3_3") (pintype "passive"))
      (node (ref "RLY8") (pin "11") (pinfunction "NC2_11") (pintype "bidirectional"))
    )
    (net (code "97") (name "Net-(RLY8-NO1)") (class "Default")
      (node (ref "JP8") (pin "2") (pinfunction "2_2") (pintype "passive"))
      (node (ref "NO8") (pin "1") (pinfunction "1_1") (pintype "passive"))
      (node (ref "RLY8") (pin "8") (pinfunction "NO1_8") (pintype "bidirectional"))
    )
    (net (code "98") (name "Net-(RLY8-NO2)") (class "Default")
      (node (ref "JP8") (pin "1") (pinfunction "1_1") (pintype "passive"))
      (node (ref "RLY8") (pin "9") (pinfunction "NO2_9") (pintype "bidirectional"))
    )
    (net (code "99") (name "unconnected-(ICSP-Pad6)") (class "Default")
      (node (ref "ICSP") (pin "6") (pinfunction "6_6") (pintype "passive"))
    )
    (net (code "100") (name "unconnected-(MIDI_IN-Pad1)") (class "Default")
      (node (ref "MIDI_IN") (pin "1") (pinfunction "1_1") (pintype "passive"))
    )
    (net (code "101") (name "unconnected-(MIDI_IN-Pad2)") (class "Default")
      (node (ref "MIDI_IN") (pin "2") (pinfunction "2_2") (pintype "passive"))
    )
    (net (code "102") (name "unconnected-(MIDI_IN-Pad3)") (class "Default")
      (node (ref "MIDI_IN") (pin "3") (pinfunction "3_3") (pintype "passive"))
    )
    (net (code "103") (name "unconnected-(U$1-PadRING_SW)") (class "Default")
      (node (ref "U$1") (pin "RING_SW") (pinfunction "RING_SW_RING_SW") (pintype "bidirectional"))
    )
  )
)
